# TLE5012.net
KiCad netlist of a schematic drawn in Altium Designer
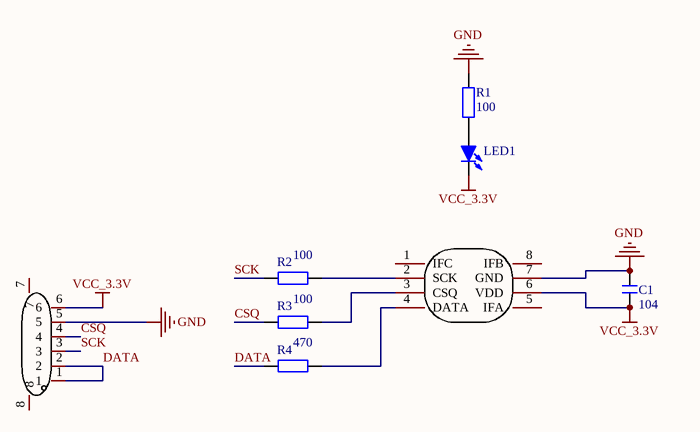
[diagram p0: TLE5012.SchDoc]

(export (version "E")
  (design (tool "Eeschema 10.0.6"))
  (components
    (comp (ref "C1")
      (value "104")
      (footprint "C0402_L")
      (description "贴片电容")
      (libsource (lib "0.1 - 电阻-电容-电感") (part "C"))
    )
    (comp (ref "CN1")
      (value "WAFER-SH1.0-6PWB")
      (footprint "SH1.0-6P")
      (fields (field (name "MANUFACTURER") "XUNPU(Ѷ��)"))
      (libsource (lib "SH1.0-6P") (part "WAFER-SH1.0-6PWB"))
    )
    (comp (ref "LED1")
      (value "~")
      (footprint "LED0603_G")
      (description "贴片LED")
      (fields (field (name "版权归属") "封装库来自淘宝 ID：黄晶宝石"))
      (libsource (lib "0.3 - LED发光二极管") (part "LED-SMD"))
    )
    (comp (ref "R1")
      (value "100")
      (footprint "R0603_L")
      (description "贴片电阻")
      (fields (field (name "版权归属") "来自淘宝 ID：黄晶宝石"))
      (libsource (lib "0.1 - 电阻-电容-电感") (part "R"))
    )
    (comp (ref "R2")
      (value "100")
      (footprint "R0805_L")
      (description "贴片电阻")
      (fields (field (name "版权归属") "来自淘宝 ID：黄晶宝石"))
      (libsource (lib "0.1 - 电阻-电容-电感") (part "R"))
    )
    (comp (ref "R3")
      (value "100")
      (footprint "R0805_L")
      (description "贴片电阻")
      (fields (field (name "版权归属") "来自淘宝 ID：黄晶宝石"))
      (libsource (lib "0.1 - 电阻-电容-电感") (part "R"))
    )
    (comp (ref "R4")
      (value "470")
      (footprint "R0805_L")
      (description "贴片电阻")
      (fields (field (name "版权归属") "来自淘宝 ID：黄晶宝石"))
      (libsource (lib "0.1 - 电阻-电容-电感") (part "R"))
    )
    (comp (ref "U1")
      (value "TLE5012BE1000")
      (footprint "PG-DSO-8_L5.0-W4.0-P1.27-LS6.0-BL")
      (fields (field (name "MANUFACTURER") "Infineon(Ӣ����)"))
      (libsource (lib "TLE5012") (part "TLE5012BE1000"))
    )
  )
  (nets
    (net (code "1") (name "/CSQ") (class "Default")
      (node (ref "CN1") (pin "4") (pinfunction "4_4") (pintype "passive"))
      (node (ref "R3") (pin "1") (pinfunction "1_1") (pintype "passive"))
    )
    (net (code "2") (name "/DATA") (class "Default")
      (node (ref "CN1") (pin "1") (pinfunction "1_1") (pintype "passive"))
      (node (ref "CN1") (pin "2") (pinfunction "2_2") (pintype "passive"))
      (node (ref "R4") (pin "1") (pinfunction "1_1") (pintype "passive"))
    )
    (net (code "3") (name "/SCK") (class "Default")
      (node (ref "CN1") (pin "3") (pinfunction "3_3") (pintype "passive"))
      (node (ref "R2") (pin "1") (pinfunction "1_1") (pintype "passive"))
    )
    (net (code "4") (name "GND") (class "Default")
      (node (ref "C1") (pin "2") (pinfunction "2_2") (pintype "passive"))
      (node (ref "CN1") (pin "5") (pinfunction "5_5") (pintype "passive"))
      (node (ref "R1") (pin "2") (pinfunction "2_2") (pintype "passive"))
      (node (ref "U1") (pin "7") (pinfunction "GND_7") (pintype "passive"))
    )
    (net (code "5") (name "Net-(LED1-A)") (class "Default")
      (node (ref "LED1") (pin "1") (pinfunction "A_1") (pintype "passive"))
      (node (ref "R1") (pin "1") (pinfunction "1_1") (pintype "passive"))
    )
    (net (code "6") (name "Net-(U1-CSQ)") (class "Default")
      (node (ref "R3") (pin "2") (pinfunction "2_2") (pintype "passive"))
      (node (ref "U1") (pin "3") (pinfunction "CSQ_3") (pintype "passive"))
    )
    (net (code "7") (name "Net-(U1-DATA)") (class "Default")
      (node (ref "R4") (pin "2") (pinfunction "2_2") (pintype "passive"))
      (node (ref "U1") (pin "4") (pinfunction "DATA_4") (pintype "passive"))
    )
    (net (code "8") (name "Net-(U1-SCK)") (class "Default")
      (node (ref "R2") (pin "2") (pinfunction "2_2") (pintype "passive"))
      (node (ref "U1") (pin "2") (pinfunction "SCK_2") (pintype "passive"))
    )
    (net (code "9") (name "VCC_3.3V") (class "Default")
      (node (ref "C1") (pin "1") (pinfunction "1_1") (pintype "passive"))
      (node (ref "CN1") (pin "6") (pinfunction "6_6") (pintype "passive"))
      (node (ref "LED1") (pin "2") (pinfunction "K_2") (pintype "passive"))
      (node (ref "U1") (pin "6") (pinfunction "VDD_6") (pintype "passive"))
    )
    (net (code "10") (name "unconnected-(CN1-Pad7)") (class "Default")
      (node (ref "CN1") (pin "7") (pinfunction "7_7") (pintype "passive"))
    )
    (net (code "11") (name "unconnected-(CN1-Pad8)") (class "Default")
      (node (ref "CN1") (pin "8") (pinfunction "8_8") (pintype "passive"))
    )
    (net (code "12") (name "unconnected-(U1-IFA-Pad5)") (class "Default")
      (node (ref "U1") (pin "5") (pinfunction "IFA_5") (pintype "passive"))
    )
    (net (code "13") (name "unconnected-(U1-IFB-Pad8)") (class "Default")
      (node (ref "U1") (pin "8") (pinfunction "IFB_8") (pintype "passive"))
    )
    (net (code "14") (name "unconnected-(U1-IFC-Pad1)") (class "Default")
      (node (ref "U1") (pin "1") (pinfunction "IFC_1") (pintype "passive"))
    )
  )
)
